# uC.net
KiCad netlist of a schematic drawn in Altium Designer
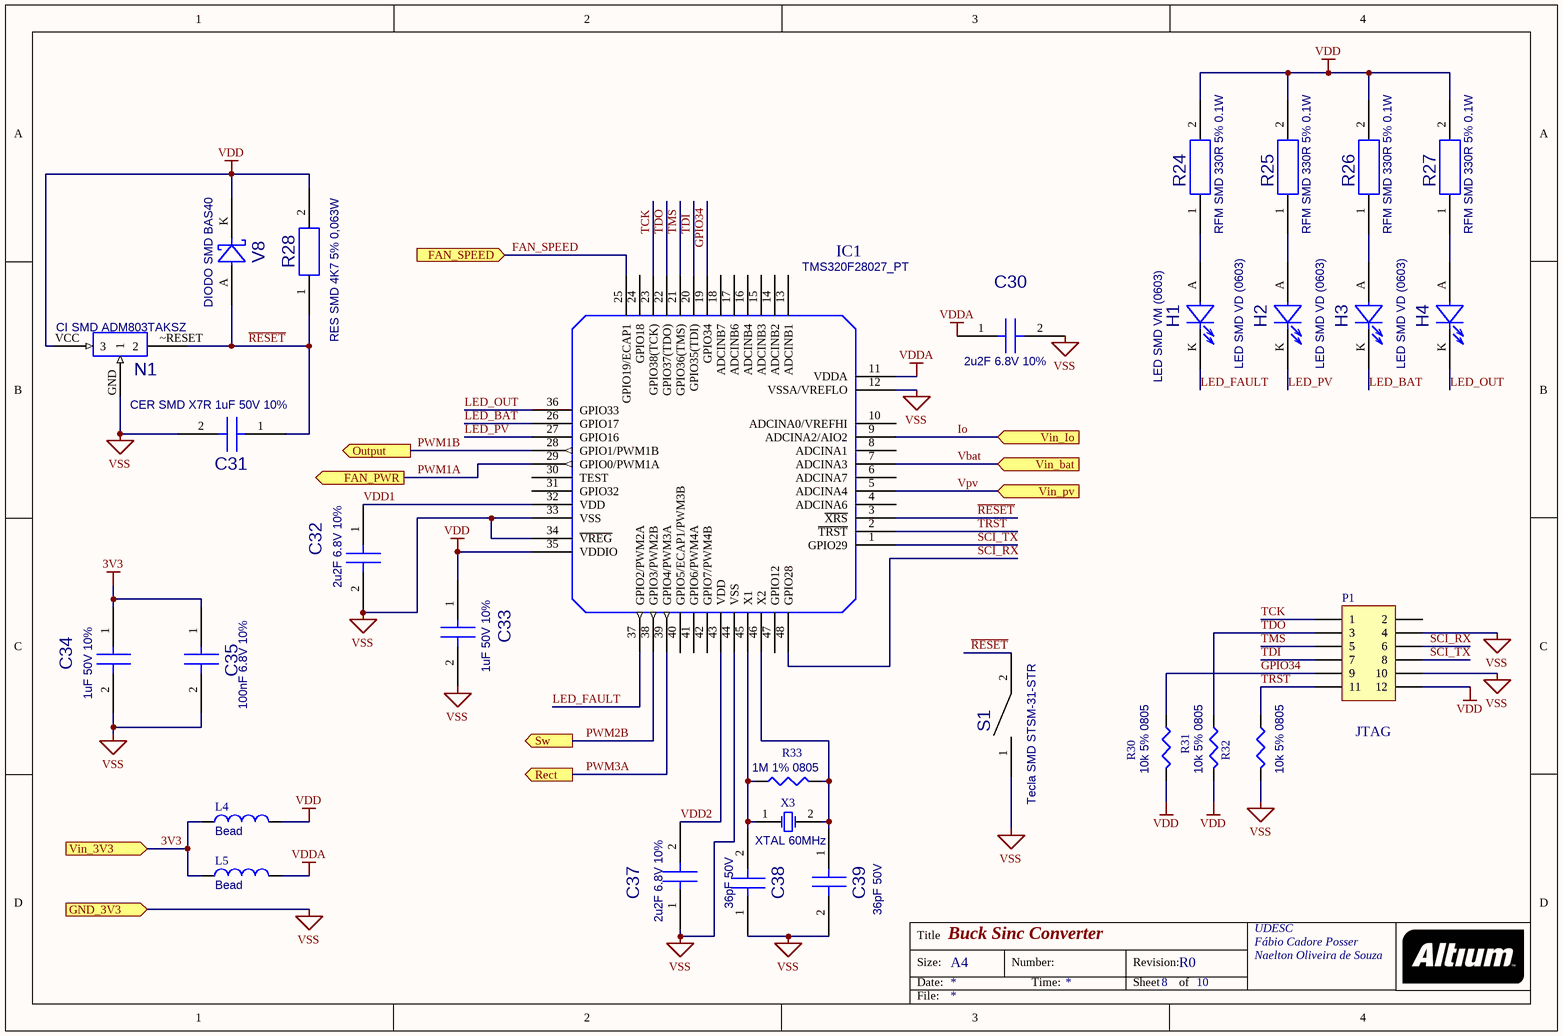
[diagram p0: uC.SchDoc]

(export (version "E")
  (design (tool "Eeschema 10.0.6"))
  (components
    (comp (ref "C30")
      (value "2u2F 6.8V 10%")
      (footprint "C0805_R_V0")
      (description "CER SMD X7R 1uF 50V 10%")
      (libsource (lib "Buck_converter") (part "11736520"))
    )
    (comp (ref "C31")
      (value "CER SMD X7R 1uF 50V 10%")
      (footprint "C0805_R_V0")
      (fields (field (name "Comment") "11736520"))
      (libsource (lib "Buck_Converter") (part "11736520"))
    )
    (comp (ref "C32")
      (value "2u2F 6.8V 10%")
      (footprint "C0805_R_V0")
      (description "CER SMD X7R 1uF 50V 10%")
      (libsource (lib "Buck_converter") (part "11736520"))
    )
    (comp (ref "C33")
      (value "1uF 50V 10%")
      (footprint "C0805_R_V0")
      (description "CER SMD X7R 1uF 50V 10%")
      (libsource (lib "Buck_converter") (part "11736520"))
    )
    (comp (ref "C34")
      (value "1uF 50V 10%")
      (footprint "C0805_R_V0")
      (description "CER SMD X7R 1uF 50V 10%")
      (libsource (lib "Buck_converter") (part "11736520"))
    )
    (comp (ref "C35")
      (value "100nF 6.8V 10%")
      (footprint "C0805_R_V0")
      (description "CER SMD X7R 1uF 50V 10%")
      (libsource (lib "Buck_converter") (part "11736520"))
    )
    (comp (ref "C37")
      (value "2u2F 6.8V 10%")
      (footprint "C0805_R_V0")
      (description "CER SMD X7R 1uF 50V 10%")
      (libsource (lib "Buck_converter") (part "11736520"))
    )
    (comp (ref "C38")
      (value "36pF 50V")
      (footprint "C0805_R_V0")
      (description "CER SMD C0G 36pF 50V")
      (libsource (lib "Buck_converter") (part "11736520"))
    )
    (comp (ref "C39")
      (value "36pF 50V")
      (footprint "C0805_R_V0")
      (description "CER SMD C0G 36pF 50V")
      (libsource (lib "Buck_converter") (part "11736520"))
    )
    (comp (ref "H1")
      (value "LED SMD VM (0603)")
      (footprint "LED 0603_12133537(Primary)")
      (fields (field (name "Comment") "12133537"))
      (libsource (lib "Buck_Converter") (part "12133537"))
    )
    (comp (ref "H2")
      (value "LED SMD VD (0603)")
      (footprint "LED 0603_12133535(Primary)")
      (fields (field (name "Comment") "12133535"))
      (libsource (lib "Buck_Converter") (part "12133535"))
    )
    (comp (ref "H3")
      (value "LED SMD VD (0603)")
      (footprint "LED 0603_12133535(Primary)")
      (fields (field (name "Comment") "12133535"))
      (libsource (lib "Buck_Converter") (part "12133535"))
    )
    (comp (ref "H4")
      (value "LED SMD VD (0603)")
      (footprint "LED 0603_12133535(Primary)")
      (fields (field (name "Comment") "12133535"))
      (libsource (lib "Buck_Converter") (part "12133535"))
    )
    (comp (ref "IC1")
      (value "TMS320F28027_PT")
      (footprint "LQFP48")
      (description "LQFP48")
      (libsource (lib "Ref_altium lib_R0") (part "TMS320F28027_PT"))
    )
    (comp (ref "L4")
      (value "Bead")
      (footprint "R0805_R_V0")
      (description "Inductor")
      (fields (field (name "PUBLISHER") "Altium Limited"))
      (libsource (lib "") (part "Inductor_1"))
    )
    (comp (ref "L5")
      (value "Bead")
      (footprint "R0805_R_V0")
      (description "Inductor")
      (fields (field (name "PUBLISHER") "Altium Limited"))
      (libsource (lib "Generic_altium lib_R0") (part "Inductor"))
    )
    (comp (ref "N1")
      (value "CI SMD ADM803TAKSZ")
      (footprint "SC70A")
      (fields (field (name "Comment") "10050567"))
      (libsource (lib "Buck_Converter") (part "10050567"))
    )
    (comp (ref "P1")
      (value "Header 6X2")
      (footprint "HDR2X6")
      (description "Header, 6-Pin, Dual row")
      (fields (field (name "PUBLISHER") "Altium Limited"))
      (libsource (lib "Miscellaneous Connectors") (part "Header 6X2"))
    )
    (comp (ref "R24")
      (value "RFM SMD 330R 5% 0.1W")
      (footprint "R0805_R_V0")
      (fields (field (name "Comment") "10191962"))
      (libsource (lib "Buck_Converter") (part "10191962"))
    )
    (comp (ref "R25")
      (value "RFM SMD 330R 5% 0.1W")
      (footprint "R0805_R_V0")
      (fields (field (name "Comment") "10191962"))
      (libsource (lib "Buck_Converter") (part "10191962"))
    )
    (comp (ref "R26")
      (value "RFM SMD 330R 5% 0.1W")
      (footprint "R0805_R_V0")
      (fields (field (name "Comment") "10191962"))
      (libsource (lib "Buck_Converter") (part "10191962"))
    )
    (comp (ref "R27")
      (value "RFM SMD 330R 5% 0.1W")
      (footprint "R0805_R_V0")
      (fields (field (name "Comment") "10191962"))
      (libsource (lib "Buck_Converter") (part "10191962"))
    )
    (comp (ref "R28")
      (value "RES SMD 4K7 5% 0,063W")
      (footprint "R0805_R_V0")
      (fields (field (name "Comment") "11417855"))
      (libsource (lib "Buck_Converter") (part "11417855"))
    )
    (comp (ref "R30")
      (value "10k 5% 0805")
      (footprint "R0805_R_V0")
      (description "Resistor")
      (fields (field (name "Comment") "1k 5% 0805") (field (name "PUBLISHER") "Altium Limited"))
      (libsource (lib "Generic_altium lib_R0") (part "Res3_2"))
    )
    (comp (ref "R31")
      (value "10k 5% 0805")
      (footprint "R0805_R_V0")
      (description "Resistor")
      (fields (field (name "Comment") "1k 5% 0805") (field (name "PUBLISHER") "Altium Limited"))
      (libsource (lib "Generic_altium lib_R0") (part "Res3_2"))
    )
    (comp (ref "R32")
      (value "10k 5% 0805")
      (footprint "R0805_R_V0")
      (description "Resistor")
      (fields (field (name "Comment") "1k 5% 0805") (field (name "PUBLISHER") "Altium Limited"))
      (libsource (lib "Generic_altium lib_R0") (part "Res3_2"))
    )
    (comp (ref "R33")
      (value "1M 1% 0805")
      (footprint "R0805_R_V0")
      (description "Resistor")
      (fields (field (name "PUBLISHER") "Altium Limited"))
      (libsource (lib "Generic_altium lib_R0") (part "Res3_2"))
    )
    (comp (ref "S1")
      (value "Tecla SMD STSM-31-STR")
      (footprint "TECLA STSM BOURNS")
      (fields (field (name "Comment") "10050610"))
      (libsource (lib "Buck_Converter") (part "10050610"))
    )
    (comp (ref "V8")
      (value "DIODO SMD BAS40")
      (footprint "SOT23A")
      (fields (field (name "Comment") "10192124"))
      (libsource (lib "Buck_Converter") (part "10192124"))
    )
    (comp (ref "X3")
      (value "XTAL 60MHz")
      (footprint "XTAL  CSTCE_G_A")
      (description "Crystal Oscillator")
      (fields (field (name "PUBLISHER") "Altium Limited"))
      (libsource (lib "Generic_altium lib_R0") (part "XTAL"))
    )
  )
  (nets
    (net (code "1") (name "/FAN_SPEED") (class "Default")
      (node (ref "IC1") (pin "25") (pinfunction "GPIO19/ECAP1_25") (pintype "power_in"))
    )
    (net (code "2") (name "/GPIO34") (class "Default")
      (node (ref "IC1") (pin "19") (pinfunction "GPIO34_19") (pintype "power_in"))
      (node (ref "P1") (pin "9") (pinfunction "9_9") (pintype "passive"))
      (node (ref "R30") (pin "1") (pinfunction "1_1") (pintype "passive"))
    )
    (net (code "3") (name "/Io") (class "Default")
      (node (ref "IC1") (pin "9") (pinfunction "ADCINA2/AIO2_9") (pintype "passive"))
    )
    (net (code "4") (name "/LED_BAT") (class "Default")
      (node (ref "H3") (pin "K") (pinfunction "K_K") (pintype "passive"))
      (node (ref "IC1") (pin "26") (pinfunction "GPIO17_26") (pintype "power_in"))
    )
    (net (code "5") (name "/LED_FAULT") (class "Default")
      (node (ref "H1") (pin "K") (pinfunction "K_K") (pintype "passive"))
      (node (ref "IC1") (pin "37") (pinfunction "GPIO2/PWM2A_37") (pintype "output"))
    )
    (net (code "6") (name "/LED_OUT") (class "Default")
      (node (ref "H4") (pin "K") (pinfunction "K_K") (pintype "passive"))
      (node (ref "IC1") (pin "36") (pinfunction "GPIO33_36") (pintype "power_in"))
    )
    (net (code "7") (name "/LED_PV") (class "Default")
      (node (ref "H2") (pin "K") (pinfunction "K_K") (pintype "passive"))
      (node (ref "IC1") (pin "27") (pinfunction "GPIO16_27") (pintype "power_in"))
    )
    (net (code "8") (name "/PWM1A") (class "Default")
      (node (ref "IC1") (pin "29") (pinfunction "GPIO0/PWM1A_29") (pintype "output"))
    )
    (net (code "9") (name "/PWM1B") (class "Default")
      (node (ref "IC1") (pin "28") (pinfunction "GPIO1/PWM1B_28") (pintype "output"))
    )
    (net (code "10") (name "/PWM2B") (class "Default")
      (node (ref "IC1") (pin "38") (pinfunction "GPIO3/PWM2B_38") (pintype "output"))
    )
    (net (code "11") (name "/PWM3A") (class "Default")
      (node (ref "IC1") (pin "39") (pinfunction "GPIO4/PWM3A_39") (pintype "output"))
    )
    (net (code "12") (name "/SCI_RX") (class "Default")
      (node (ref "IC1") (pin "48") (pinfunction "GPIO28_48") (pintype "power_in"))
      (node (ref "P1") (pin "6") (pinfunction "6_6") (pintype "passive"))
    )
    (net (code "13") (name "/SCI_TX") (class "Default")
      (node (ref "IC1") (pin "1") (pinfunction "GPIO29_1") (pintype "passive"))
      (node (ref "P1") (pin "8") (pinfunction "8_8") (pintype "passive"))
    )
    (net (code "14") (name "/TCK") (class "Default")
      (node (ref "IC1") (pin "23") (pinfunction "GPIO38(TCK)_23") (pintype "power_in"))
      (node (ref "P1") (pin "1") (pinfunction "1_1") (pintype "passive"))
    )
    (net (code "15") (name "/TDI") (class "Default")
      (node (ref "IC1") (pin "20") (pinfunction "GPIO35(TDI)_20") (pintype "power_in"))
      (node (ref "P1") (pin "7") (pinfunction "7_7") (pintype "passive"))
    )
    (net (code "16") (name "/TDO") (class "Default")
      (node (ref "IC1") (pin "22") (pinfunction "GPIO37(TDO)_22") (pintype "power_in"))
      (node (ref "P1") (pin "3") (pinfunction "3_3") (pintype "passive"))
      (node (ref "R31") (pin "1") (pinfunction "1_1") (pintype "passive"))
    )
    (net (code "17") (name "/TMS") (class "Default")
      (node (ref "IC1") (pin "21") (pinfunction "GPIO36(TMS)_21") (pintype "power_in"))
      (node (ref "P1") (pin "5") (pinfunction "5_5") (pintype "passive"))
    )
    (net (code "18") (name "/TRST") (class "Default")
      (node (ref "IC1") (pin "2") (pinfunction "~{TRST}_2") (pintype "passive"))
      (node (ref "P1") (pin "11") (pinfunction "11_11") (pintype "passive"))
      (node (ref "R32") (pin "1") (pinfunction "1_1") (pintype "passive"))
    )
    (net (code "19") (name "/VDD1") (class "Default")
      (node (ref "C32") (pin "1") (pinfunction "1_1") (pintype "passive"))
      (node (ref "IC1") (pin "32") (pinfunction "VDD_32") (pintype "power_in"))
    )
    (net (code "20") (name "/VDD2") (class "Default")
      (node (ref "C37") (pin "2") (pinfunction "2_2") (pintype "passive"))
      (node (ref "IC1") (pin "43") (pinfunction "VDD_43") (pintype "power_in"))
    )
    (net (code "21") (name "/Vbat") (class "Default")
      (node (ref "IC1") (pin "7") (pinfunction "ADCINA3_7") (pintype "passive"))
    )
    (net (code "22") (name "/Vpv") (class "Default")
      (node (ref "IC1") (pin "5") (pinfunction "ADCINA4_5") (pintype "passive"))
    )
    (net (code "23") (name "/~{RESET}") (class "Default")
      (node (ref "C31") (pin "1") (pinfunction "1_1") (pintype "passive"))
      (node (ref "IC1") (pin "3") (pinfunction "~{XRS}_3") (pintype "passive"))
      (node (ref "N1") (pin "~RESET") (pinfunction "2_~RESET") (pintype "passive"))
      (node (ref "R28") (pin "1") (pinfunction "1_1") (pintype "passive"))
      (node (ref "S1") (pin "2") (pinfunction "2_2") (pintype "passive"))
      (node (ref "V8") (pin "A") (pinfunction "A_A") (pintype "passive"))
    )
    (net (code "24") (name "3V3") (class "Default")
      (node (ref "C34") (pin "1") (pinfunction "1_1") (pintype "passive"))
      (node (ref "C35") (pin "1") (pinfunction "1_1") (pintype "passive"))
      (node (ref "L4") (pin "1") (pinfunction "1_1") (pintype "passive"))
      (node (ref "L5") (pin "2") (pinfunction "2_2") (pintype "passive"))
    )
    (net (code "25") (name "Net-(H1-PadA)") (class "Default")
      (node (ref "H1") (pin "A") (pinfunction "A_A") (pintype "passive"))
      (node (ref "R24") (pin "1") (pinfunction "1_1") (pintype "passive"))
    )
    (net (code "26") (name "Net-(H2-PadA)") (class "Default")
      (node (ref "H2") (pin "A") (pinfunction "A_A") (pintype "passive"))
      (node (ref "R25") (pin "1") (pinfunction "1_1") (pintype "passive"))
    )
    (net (code "27") (name "Net-(H3-PadA)") (class "Default")
      (node (ref "H3") (pin "A") (pinfunction "A_A") (pintype "passive"))
      (node (ref "R26") (pin "1") (pinfunction "1_1") (pintype "passive"))
    )
    (net (code "28") (name "Net-(H4-PadA)") (class "Default")
      (node (ref "H4") (pin "A") (pinfunction "A_A") (pintype "passive"))
      (node (ref "R27") (pin "1") (pinfunction "1_1") (pintype "passive"))
    )
    (net (code "29") (name "Net-(IC1-X1)") (class "Default")
      (node (ref "C38") (pin "2") (pinfunction "2_2") (pintype "passive"))
      (node (ref "IC1") (pin "45") (pinfunction "X1_45") (pintype "power_in"))
      (node (ref "R33") (pin "1") (pinfunction "1_1") (pintype "passive"))
      (node (ref "X3") (pin "1") (pinfunction "OSC1_1") (pintype "passive"))
    )
    (net (code "30") (name "Net-(IC1-X2)") (class "Default")
      (node (ref "C39") (pin "1") (pinfunction "1_1") (pintype "passive"))
      (node (ref "IC1") (pin "46") (pinfunction "X2_46") (pintype "power_in"))
      (node (ref "R33") (pin "2") (pinfunction "2_2") (pintype "passive"))
      (node (ref "X3") (pin "2") (pinfunction "OSC2_2") (pintype "passive"))
    )
    (net (code "31") (name "VDD") (class "Default")
      (node (ref "C33") (pin "1") (pinfunction "1_1") (pintype "passive"))
      (node (ref "IC1") (pin "35") (pinfunction "VDDIO_35") (pintype "power_in"))
      (node (ref "L4") (pin "2") (pinfunction "2_2") (pintype "passive"))
      (node (ref "N1") (pin "VCC") (pinfunction "3_VCC") (pintype "input"))
      (node (ref "P1") (pin "12") (pinfunction "12_12") (pintype "passive"))
      (node (ref "R24") (pin "2") (pinfunction "2_2") (pintype "passive"))
      (node (ref "R25") (pin "2") (pinfunction "2_2") (pintype "passive"))
      (node (ref "R26") (pin "2") (pinfunction "2_2") (pintype "passive"))
      (node (ref "R27") (pin "2") (pinfunction "2_2") (pintype "passive"))
      (node (ref "R28") (pin "2") (pinfunction "2_2") (pintype "passive"))
      (node (ref "R30") (pin "2") (pinfunction "2_2") (pintype "passive"))
      (node (ref "R31") (pin "2") (pinfunction "2_2") (pintype "passive"))
      (node (ref "V8") (pin "K") (pinfunction "K_K") (pintype "passive"))
    )
    (net (code "32") (name "VDDA") (class "Default")
      (node (ref "C30") (pin "1") (pinfunction "1_1") (pintype "passive"))
      (node (ref "IC1") (pin "11") (pinfunction "VDDA_11") (pintype "power_in"))
      (node (ref "L5") (pin "1") (pinfunction "1_1") (pintype "passive"))
    )
    (net (code "33") (name "VSS") (class "Default")
      (node (ref "C30") (pin "2") (pinfunction "2_2") (pintype "passive"))
      (node (ref "C31") (pin "2") (pinfunction "2_2") (pintype "passive"))
      (node (ref "C32") (pin "2") (pinfunction "2_2") (pintype "passive"))
      (node (ref "C33") (pin "2") (pinfunction "2_2") (pintype "passive"))
      (node (ref "C34") (pin "2") (pinfunction "2_2") (pintype "passive"))
      (node (ref "C35") (pin "2") (pinfunction "2_2") (pintype "passive"))
      (node (ref "C37") (pin "1") (pinfunction "1_1") (pintype "passive"))
      (node (ref "C38") (pin "1") (pinfunction "1_1") (pintype "passive"))
      (node (ref "C39") (pin "2") (pinfunction "2_2") (pintype "passive"))
      (node (ref "IC1") (pin "12") (pinfunction "VSSA/VREFLO_12") (pintype "power_in"))
      (node (ref "IC1") (pin "33") (pinfunction "VSS_33") (pintype "power_in"))
      (node (ref "IC1") (pin "34") (pinfunction "~{VREG}_34") (pintype "power_in"))
      (node (ref "IC1") (pin "44") (pinfunction "VSS_44") (pintype "power_in"))
      (node (ref "N1") (pin "GND") (pinfunction "1_GND") (pintype "input"))
      (node (ref "P1") (pin "10") (pinfunction "10_10") (pintype "passive"))
      (node (ref "P1") (pin "4") (pinfunction "4_4") (pintype "passive"))
      (node (ref "R32") (pin "2") (pinfunction "2_2") (pintype "passive"))
      (node (ref "S1") (pin "1") (pinfunction "1_1") (pintype "passive"))
    )
    (net (code "34") (name "unconnected-(IC1-ADCINA0{slash}VREFHI-Pad10)") (class "Default")
      (node (ref "IC1") (pin "10") (pinfunction "ADCINA0/VREFHI_10") (pintype "passive"))
    )
    (net (code "35") (name "unconnected-(IC1-ADCINA1-Pad8)") (class "Default")
      (node (ref "IC1") (pin "8") (pinfunction "ADCINA1_8") (pintype "passive"))
    )
    (net (code "36") (name "unconnected-(IC1-ADCINA6-Pad4)") (class "Default")
      (node (ref "IC1") (pin "4") (pinfunction "ADCINA6_4") (pintype "passive"))
    )
    (net (code "37") (name "unconnected-(IC1-ADCINA7-Pad6)") (class "Default")
      (node (ref "IC1") (pin "6") (pinfunction "ADCINA7_6") (pintype "passive"))
    )
    (net (code "38") (name "unconnected-(IC1-ADCINB1-Pad13)") (class "Default")
      (node (ref "IC1") (pin "13") (pinfunction "ADCINB1_13") (pintype "power_in"))
    )
    (net (code "39") (name "unconnected-(IC1-ADCINB2-Pad14)") (class "Default")
      (node (ref "IC1") (pin "14") (pinfunction "ADCINB2_14") (pintype "power_in"))
    )
    (net (code "40") (name "unconnected-(IC1-ADCINB3-Pad15)") (class "Default")
      (node (ref "IC1") (pin "15") (pinfunction "ADCINB3_15") (pintype "power_in"))
    )
    (net (code "41") (name "unconnected-(IC1-ADCINB4-Pad16)") (class "Default")
      (node (ref "IC1") (pin "16") (pinfunction "ADCINB4_16") (pintype "power_in"))
    )
    (net (code "42") (name "unconnected-(IC1-ADCINB6-Pad17)") (class "Default")
      (node (ref "IC1") (pin "17") (pinfunction "ADCINB6_17") (pintype "power_in"))
    )
    (net (code "43") (name "unconnected-(IC1-ADCINB7-Pad18)") (class "Default")
      (node (ref "IC1") (pin "18") (pinfunction "ADCINB7_18") (pintype "power_in"))
    )
    (net (code "44") (name "unconnected-(IC1-GPIO5{slash}ECAP1{slash}PWM3B-Pad40)") (class "Default")
      (node (ref "IC1") (pin "40") (pinfunction "GPIO5/ECAP1/PWM3B_40") (pintype "power_in"))
    )
    (net (code "45") (name "unconnected-(IC1-GPIO6{slash}PWM4A-Pad41)") (class "Default")
      (node (ref "IC1") (pin "41") (pinfunction "GPIO6/PWM4A_41") (pintype "power_in"))
    )
    (net (code "46") (name "unconnected-(IC1-GPIO7{slash}PWM4B-Pad42)") (class "Default")
      (node (ref "IC1") (pin "42") (pinfunction "GPIO7/PWM4B_42") (pintype "power_in"))
    )
    (net (code "47") (name "unconnected-(IC1-GPIO12-Pad47)") (class "Default")
      (node (ref "IC1") (pin "47") (pinfunction "GPIO12_47") (pintype "power_in"))
    )
    (net (code "48") (name "unconnected-(IC1-GPIO18-Pad24)") (class "Default")
      (node (ref "IC1") (pin "24") (pinfunction "GPIO18_24") (pintype "power_in"))
    )
    (net (code "49") (name "unconnected-(IC1-GPIO32-Pad31)") (class "Default")
      (node (ref "IC1") (pin "31") (pinfunction "GPIO32_31") (pintype "power_in"))
    )
    (net (code "50") (name "unconnected-(IC1-TEST-Pad30)") (class "Default")
      (node (ref "IC1") (pin "30") (pinfunction "TEST_30") (pintype "power_in"))
    )
    (net (code "51") (name "unconnected-(P1-Pad2)") (class "Default")
      (node (ref "P1") (pin "2") (pinfunction "2_2") (pintype "passive"))
    )
    (net (code "52") (name "unconnected-(V8-PadNC)") (class "Default")
      (node (ref "V8") (pin "NC") (pintype "passive"))
    )
  )
)
